# GPIO.net
KiCad netlist of a schematic drawn in Altium Designer
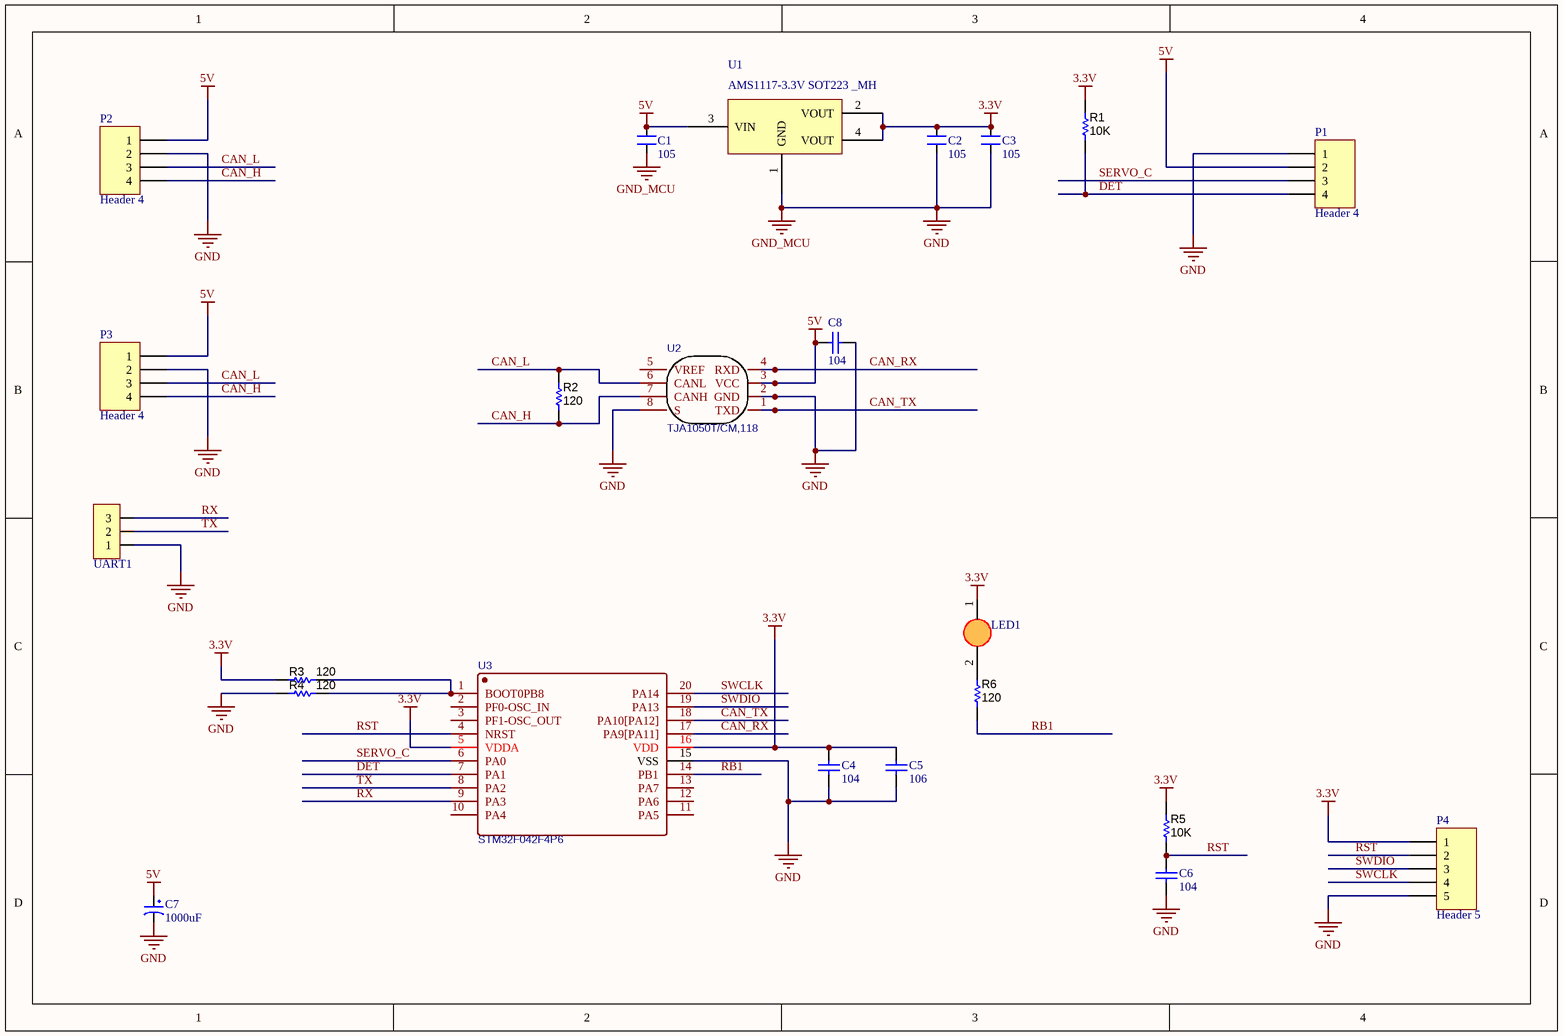
[diagram p0: GPIO.SchDoc]

(export (version "E")
  (design (tool "Eeschema 10.0.6"))
  (components
    (comp (ref "C1")
      (value "105")
      (footprint "0805_HV")
      (description "Cap SMD")
      (libsource (lib "hatcatbietbay") (part "CM"))
    )
    (comp (ref "C2")
      (value "105")
      (footprint "0805_HV")
      (description "Cap SMD")
      (libsource (lib "hatcatbietbay") (part "CM"))
    )
    (comp (ref "C3")
      (value "105")
      (footprint "0805_HV")
      (description "Cap SMD")
      (libsource (lib "hatcatbietbay") (part "CM"))
    )
    (comp (ref "C4")
      (value "104")
      (footprint "0805_HV")
      (description "Ceramic Chip Capacitor - Standard")
      (fields (field (name "PUBLISHER") "Altium Limited"))
      (libsource (lib "mySch") (part "Capacitor 0805"))
    )
    (comp (ref "C5")
      (value "106")
      (footprint "0805_HV")
      (description "Ceramic Chip Capacitor - Standard")
      (fields (field (name "PUBLISHER") "Altium Limited"))
      (libsource (lib "mySch") (part "Capacitor 0805"))
    )
    (comp (ref "C6")
      (value "104")
      (footprint "0805_HV")
      (description "Ceramic Chip Capacitor - Standard")
      (fields (field (name "PUBLISHER") "Altium Limited"))
      (libsource (lib "mySch") (part "Capacitor 0805"))
    )
    (comp (ref "C7")
      (value "1000uF")
      (footprint "TU_NHOM_470uF_25V_MH")
      (description "TU_NHOM_1000uF_16V_MH")
      (libsource (lib "MH_DA_THU_VIEN_16122016") (part "TU_NHOM_1000uF_16V_MH"))
    )
    (comp (ref "C8")
      (value "104")
      (footprint "0805_HV")
      (description "Ceramic Chip Capacitor - Standard")
      (fields (field (name "PUBLISHER") "Altium Limited"))
      (libsource (lib "mySch") (part "Capacitor 0805"))
    )
    (comp (ref "LED1")
      (value "LED3")
      (footprint "LED_0805")
      (description "LED 3mm")
      (libsource (lib "MH_DA_THU_VIEN_16122016") (part "LED SMD_0805_MH"))
    )
    (comp (ref "P1")
      (value "Header 4")
      (footprint "SpringCON")
      (description "Header, 4-Pin")
      (fields (field (name "PUBLISHER") "Altium Limited"))
      (libsource (lib "") (part "Header 4_1"))
    )
    (comp (ref "P2")
      (value "Header 4")
      (footprint "JST-PH2.00-4P")
      (description "Header, 4-Pin")
      (fields (field (name "PUBLISHER") "Altium Limited"))
      (libsource (lib "Miscellaneous Connectors") (part "Header 4"))
    )
    (comp (ref "P3")
      (value "Header 4")
      (footprint "JST-PH2.00-4P")
      (description "Header, 4-Pin")
      (fields (field (name "PUBLISHER") "Altium Limited"))
      (libsource (lib "Miscellaneous Connectors") (part "Header 4"))
    )
    (comp (ref "P4")
      (value "Header 5")
      (footprint "HDR1X5")
      (description "Header, 5-Pin")
      (fields (field (name "PUBLISHER") "Altium Limited"))
      (libsource (lib "Miscellaneous Connectors") (part "Header 5"))
    )
    (comp (ref "R1")
      (value "10K")
      (footprint "Tro SMD 0805")
      (description "RES, 100, 1%, 0.1 W, 0402")
      (fields
        (field (name "PARTNUMBER") "ERJ-2RKF1000X")
        (field (name "MANUFACTURER") "Panasonic")
        (field (name "PUBLISHER") "Texas Instruments")
      )
      (libsource (lib "mySch") (part "R nho"))
    )
    (comp (ref "R2")
      (value "120")
      (footprint "0805_HV")
      (description "RES, 100, 1%, 0.1 W, 0402")
      (fields
        (field (name "PARTNUMBER") "ERJ-2RKF1000X")
        (field (name "MANUFACTURER") "Panasonic")
        (field (name "PUBLISHER") "Texas Instruments")
      )
      (libsource (lib "mySch") (part "R nho"))
    )
    (comp (ref "R3")
      (value "120")
      (footprint "0805_HV")
      (description "RES, 100, 1%, 0.1 W, 0402")
      (fields
        (field (name "PARTNUMBER") "ERJ-2RKF1000X")
        (field (name "MANUFACTURER") "Panasonic")
        (field (name "PUBLISHER") "Texas Instruments")
      )
      (libsource (lib "mySch") (part "R nho"))
    )
    (comp (ref "R4")
      (value "120")
      (footprint "0805_HV")
      (description "RES, 100, 1%, 0.1 W, 0402")
      (fields
        (field (name "PARTNUMBER") "ERJ-2RKF1000X")
        (field (name "MANUFACTURER") "Panasonic")
        (field (name "PUBLISHER") "Texas Instruments")
      )
      (libsource (lib "mySch") (part "R nho"))
    )
    (comp (ref "R5")
      (value "10K")
      (footprint "0805_HV")
      (description "RES, 100, 1%, 0.1 W, 0402")
      (fields
        (field (name "PARTNUMBER") "ERJ-2RKF1000X")
        (field (name "MANUFACTURER") "Panasonic")
        (field (name "PUBLISHER") "Texas Instruments")
      )
      (libsource (lib "mySch") (part "R nho"))
    )
    (comp (ref "R6")
      (value "120")
      (footprint "0805_HV")
      (description "RES, 100, 1%, 0.1 W, 0402")
      (fields
        (field (name "PARTNUMBER") "ERJ-2RKF1000X")
        (field (name "MANUFACTURER") "Panasonic")
        (field (name "PUBLISHER") "Texas Instruments")
      )
      (libsource (lib "mySch") (part "R nho"))
    )
    (comp (ref "U1")
      (value "AMS1117-3.3V SOT223 _MH")
      (footprint "SOT223")
      (libsource (lib "MH_DA_THU_VIEN_16122016") (part "AMS1117-3.3V SOT223 _MH"))
    )
    (comp (ref "U2")
      (value "TJA1050T/CM,118")
      (footprint "SOP 8")
      (fields (field (name "BOM_SUPPLIER PART") "C6952"))
      (libsource (lib "Schlib1") (part "TJA1050T/CM,118"))
    )
    (comp (ref "U3")
      (value "STM32F042F4P6")
      (footprint "TSSOP20")
      (fields (field (name "BOM_SUPPLIER PART") "C81002"))
      (libsource (lib "Schlib1") (part "STM32F042F4P6"))
    )
    (comp (ref "UART1")
      (value "Header 3_MH")
      (footprint "HEADER 3")
      (description "Header 3P XH2.54 thẳng")
      (libsource (lib "MH_DA_THU_VIEN_16122016") (part "Header 3_MH"))
    )
  )
  (nets
    (net (code "1") (name "/CAN_H") (class "Default")
      (node (ref "P2") (pin "4") (pinfunction "4_4") (pintype "passive"))
      (node (ref "P3") (pin "4") (pinfunction "4_4") (pintype "passive"))
      (node (ref "R2") (pin "2") (pinfunction "2_2") (pintype "passive"))
      (node (ref "U2") (pin "7") (pinfunction "CANH_7") (pintype "passive"))
    )
    (net (code "2") (name "/CAN_L") (class "Default")
      (node (ref "P2") (pin "3") (pinfunction "3_3") (pintype "passive"))
      (node (ref "P3") (pin "3") (pinfunction "3_3") (pintype "passive"))
      (node (ref "R2") (pin "1") (pinfunction "1_1") (pintype "passive"))
      (node (ref "U2") (pin "6") (pinfunction "CANL_6") (pintype "passive"))
    )
    (net (code "3") (name "/CAN_RX") (class "Default")
      (node (ref "U2") (pin "4") (pinfunction "RXD_4") (pintype "passive"))
      (node (ref "U3") (pin "17") (pinfunction "PA9[PA11]_17") (pintype "passive"))
    )
    (net (code "4") (name "/CAN_TX") (class "Default")
      (node (ref "U2") (pin "1") (pinfunction "TXD_1") (pintype "passive"))
      (node (ref "U3") (pin "18") (pinfunction "PA10[PA12]_18") (pintype "passive"))
    )
    (net (code "5") (name "/DET") (class "Default")
      (node (ref "P1") (pin "4") (pinfunction "4_4") (pintype "passive"))
      (node (ref "R1") (pin "2") (pinfunction "2_2") (pintype "passive"))
      (node (ref "U3") (pin "7") (pinfunction "PA1_7") (pintype "passive"))
    )
    (net (code "6") (name "/RB1") (class "Default")
      (node (ref "R6") (pin "2") (pinfunction "2_2") (pintype "passive"))
      (node (ref "U3") (pin "14") (pinfunction "PB1_14") (pintype "passive"))
    )
    (net (code "7") (name "/RST") (class "Default")
      (node (ref "C6") (pin "2") (pinfunction "2_2") (pintype "passive"))
      (node (ref "P4") (pin "2") (pinfunction "2_2") (pintype "passive"))
      (node (ref "R5") (pin "1") (pinfunction "1_1") (pintype "passive"))
      (node (ref "U3") (pin "4") (pinfunction "NRST_4") (pintype "passive"))
    )
    (net (code "8") (name "/RX") (class "Default")
      (node (ref "U3") (pin "9") (pinfunction "PA3_9") (pintype "passive"))
      (node (ref "UART1") (pin "3") (pinfunction "3_3") (pintype "passive"))
    )
    (net (code "9") (name "/SERVO_C") (class "Default")
      (node (ref "P1") (pin "3") (pinfunction "3_3") (pintype "passive"))
      (node (ref "U3") (pin "6") (pinfunction "PA0_6") (pintype "passive"))
    )
    (net (code "10") (name "/SWCLK") (class "Default")
      (node (ref "P4") (pin "4") (pinfunction "4_4") (pintype "passive"))
      (node (ref "U3") (pin "20") (pinfunction "PA14_20") (pintype "passive"))
    )
    (net (code "11") (name "/SWDIO") (class "Default")
      (node (ref "P4") (pin "3") (pinfunction "3_3") (pintype "passive"))
      (node (ref "U3") (pin "19") (pinfunction "PA13_19") (pintype "passive"))
    )
    (net (code "12") (name "/TX") (class "Default")
      (node (ref "U3") (pin "8") (pinfunction "PA2_8") (pintype "passive"))
      (node (ref "UART1") (pin "2") (pinfunction "2_2") (pintype "passive"))
    )
    (net (code "13") (name "3.3V") (class "Default")
      (node (ref "C2") (pin "2") (pinfunction "2_2") (pintype "passive"))
      (node (ref "C3") (pin "2") (pinfunction "2_2") (pintype "passive"))
      (node (ref "C4") (pin "2") (pinfunction "2_2") (pintype "passive"))
      (node (ref "C5") (pin "2") (pinfunction "2_2") (pintype "passive"))
      (node (ref "LED1") (pin "1") (pinfunction "A_1") (pintype "passive"))
      (node (ref "P4") (pin "1") (pinfunction "1_1") (pintype "passive"))
      (node (ref "R1") (pin "1") (pinfunction "1_1") (pintype "passive"))
      (node (ref "R3") (pin "1") (pinfunction "1_1") (pintype "passive"))
      (node (ref "R5") (pin "2") (pinfunction "2_2") (pintype "passive"))
      (node (ref "U1") (pin "2") (pinfunction "VOUT_2") (pintype "passive"))
      (node (ref "U1") (pin "4") (pinfunction "VOUT_4") (pintype "passive"))
      (node (ref "U3") (pin "16") (pinfunction "VDD_16") (pintype "passive"))
      (node (ref "U3") (pin "5") (pinfunction "VDDA_5") (pintype "passive"))
    )
    (net (code "14") (name "5V") (class "Default")
      (node (ref "C1") (pin "2") (pinfunction "2_2") (pintype "passive"))
      (node (ref "C7") (pin "1") (pinfunction "1_1") (pintype "passive"))
      (node (ref "C8") (pin "2") (pinfunction "2_2") (pintype "passive"))
      (node (ref "P1") (pin "2") (pinfunction "2_2") (pintype "passive"))
      (node (ref "P2") (pin "1") (pinfunction "1_1") (pintype "passive"))
      (node (ref "P3") (pin "1") (pinfunction "1_1") (pintype "passive"))
      (node (ref "U1") (pin "3") (pinfunction "VIN_3") (pintype "passive"))
      (node (ref "U2") (pin "3") (pinfunction "VCC_3") (pintype "passive"))
    )
    (net (code "15") (name "GND") (class "Default")
      (node (ref "C1") (pin "1") (pinfunction "1_1") (pintype "passive"))
      (node (ref "C2") (pin "1") (pinfunction "1_1") (pintype "passive"))
      (node (ref "C3") (pin "1") (pinfunction "1_1") (pintype "passive"))
      (node (ref "C4") (pin "1") (pinfunction "1_1") (pintype "passive"))
      (node (ref "C5") (pin "1") (pinfunction "1_1") (pintype "passive"))
      (node (ref "C6") (pin "1") (pinfunction "1_1") (pintype "passive"))
      (node (ref "C7") (pin "2") (pinfunction "2_2") (pintype "passive"))
      (node (ref "C8") (pin "1") (pinfunction "1_1") (pintype "passive"))
      (node (ref "P1") (pin "1") (pinfunction "1_1") (pintype "passive"))
      (node (ref "P2") (pin "2") (pinfunction "2_2") (pintype "passive"))
      (node (ref "P3") (pin "2") (pinfunction "2_2") (pintype "passive"))
      (node (ref "P4") (pin "5") (pinfunction "5_5") (pintype "passive"))
      (node (ref "R4") (pin "1") (pinfunction "1_1") (pintype "passive"))
      (node (ref "U1") (pin "1") (pinfunction "GND_1") (pintype "passive"))
      (node (ref "U2") (pin "2") (pinfunction "GND_2") (pintype "passive"))
      (node (ref "U2") (pin "8") (pinfunction "S_8") (pintype "passive"))
      (node (ref "U3") (pin "15") (pinfunction "VSS_15") (pintype "passive"))
      (node (ref "UART1") (pin "1") (pinfunction "1_1") (pintype "passive"))
    )
    (net (code "16") (name "Net-(LED1-K)") (class "Default")
      (node (ref "LED1") (pin "2") (pinfunction "K_2") (pintype "passive"))
      (node (ref "R6") (pin "1") (pinfunction "1_1") (pintype "passive"))
    )
    (net (code "17") (name "Net-(U3-BOOT0PB8)") (class "Default")
      (node (ref "R3") (pin "2") (pinfunction "2_2") (pintype "passive"))
      (node (ref "R4") (pin "2") (pinfunction "2_2") (pintype "passive"))
      (node (ref "U3") (pin "1") (pinfunction "BOOT0PB8_1") (pintype "passive"))
    )
    (net (code "18") (name "unconnected-(U2-VREF-Pad5)") (class "Default")
      (node (ref "U2") (pin "5") (pinfunction "VREF_5") (pintype "passive"))
    )
    (net (code "19") (name "unconnected-(U3-PA4-Pad10)") (class "Default")
      (node (ref "U3") (pin "10") (pinfunction "PA4_10") (pintype "passive"))
    )
    (net (code "20") (name "unconnected-(U3-PA5-Pad11)") (class "Default")
      (node (ref "U3") (pin "11") (pinfunction "PA5_11") (pintype "passive"))
    )
    (net (code "21") (name "unconnected-(U3-PA6-Pad12)") (class "Default")
      (node (ref "U3") (pin "12") (pinfunction "PA6_12") (pintype "passive"))
    )
    (net (code "22") (name "unconnected-(U3-PA7-Pad13)") (class "Default")
      (node (ref "U3") (pin "13") (pinfunction "PA7_13") (pintype "passive"))
    )
    (net (code "23") (name "unconnected-(U3-PF0-OSC_IN-Pad2)") (class "Default")
      (node (ref "U3") (pin "2") (pinfunction "PF0-OSC_IN_2") (pintype "passive"))
    )
    (net (code "24") (name "unconnected-(U3-PF1-OSC_OUT-Pad3)") (class "Default")
      (node (ref "U3") (pin "3") (pinfunction "PF1-OSC_OUT_3") (pintype "passive"))
    )
  )
)
